# ESC.net
KiCad netlist of a schematic drawn in Altium Designer
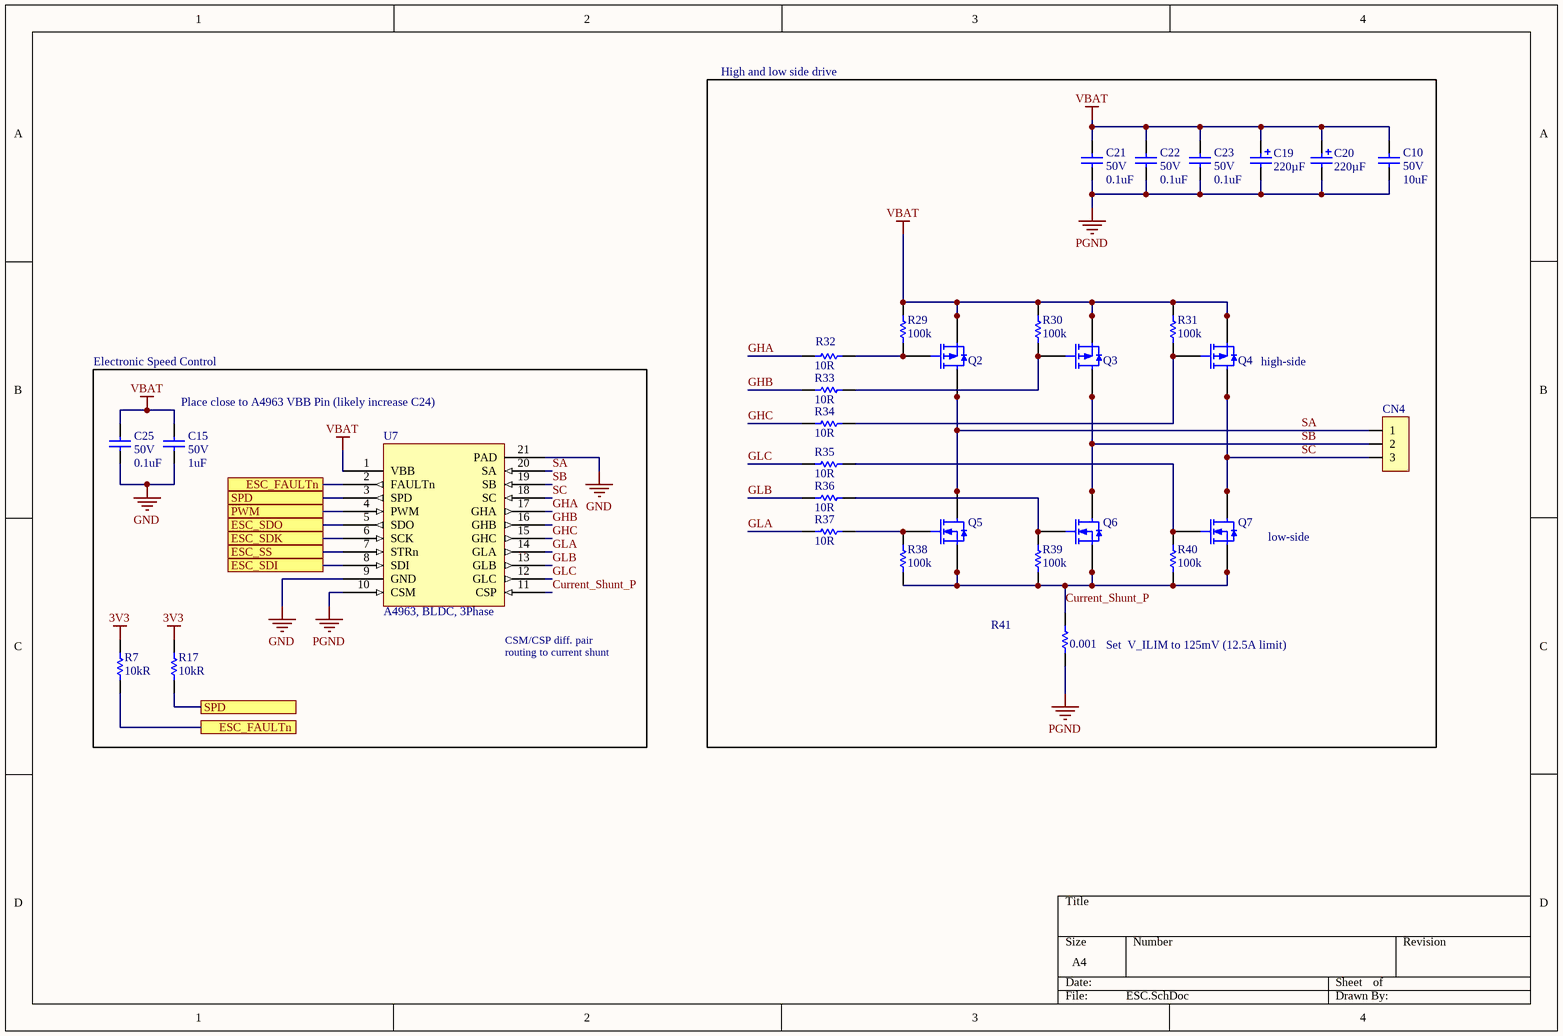
[diagram p0: ESC.SchDoc]

(export (version "E")
  (design (tool "Eeschema 10.0.6"))
  (components
    (comp (ref "C10")
      (value "CL31B106KBHNNNE")
      (footprint "CAPC3216X180X50ML20T30")
      (description "Cap Ceramic 10uF 50V X7R 10% Pad SMD 1206 125°C T/R")
      (fields
        (field (name "VOLTAGE RATING (DC)") "50V")
        (field (name "CAPACITANCE") "10uF")
        (field (name "TOLERANCE") "10%")
      )
      (libsource (lib "AUVIC") (part "CAP-NP-2"))
    )
    (comp (ref "C15")
      (value "CL21B105KBFNNNG")
      (footprint "0803 CAP")
      (description "SAMSUNG ELECTRO-MECHANICS - CL21B105KBFNNNG - MLCC CAPACITORS")
      (fields
        (field (name "CAPACITANCE") "1uF")
        (field (name "TOLERANCE") "10%")
        (field (name "VOLTAGE") "50V")
      )
      (libsource (lib "") (part "Symbol_3"))
    )
    (comp (ref "C19")
      (value "220µF")
      (footprint "Radial_CAN_8.3mm_10.5mm")
      (description "Capacitor, Polarized, Aluminum, 50V")
      (fields
        (field (name "Comment") "220uF, 50V, 20%, Alum, Polarized, SMD")
        (field (name "PUBLISHER") "AUVic")
        (field (name "CREATED BY") "Ashwin Sira")
      )
      (libsource (lib "AUVIC") (part "Symbol"))
    )
    (comp (ref "C20")
      (value "220µF")
      (footprint "Radial_CAN_8.3mm_10.5mm")
      (description "Capacitor, Polarized, Aluminum, 50V")
      (fields
        (field (name "Comment") "220uF, 50V, 20%, Alum, Polarized, SMD")
        (field (name "PUBLISHER") "AUVic")
        (field (name "CREATED BY") "Ashwin Sira")
      )
      (libsource (lib "AUVIC") (part "Symbol"))
    )
    (comp (ref "C21")
      (value "CL10B104JB8NNNC")
      (footprint "FP-CL10-0_1-MFG")
      (description "CAP CER 0.1UF 50V X7R 0603")
      (fields
        (field (name "TOLERANCE") "5%")
        (field (name "VOLTAGE") "50V")
        (field (name "CAPACITANCE") "0.1uF")
      )
      (libsource (lib "AUVIC") (part "CAP-NP-2"))
    )
    (comp (ref "C22")
      (value "CL10B104JB8NNNC")
      (footprint "FP-CL10-0_1-MFG")
      (description "CAP CER 0.1UF 50V X7R 0603")
      (fields
        (field (name "TOLERANCE") "5%")
        (field (name "VOLTAGE") "50V")
        (field (name "CAPACITANCE") "0.1uF")
      )
      (libsource (lib "AUVIC") (part "CAP-NP-2"))
    )
    (comp (ref "C23")
      (value "CL10B104JB8NNNC")
      (footprint "FP-CL10-0_1-MFG")
      (description "CAP CER 0.1UF 50V X7R 0603")
      (fields
        (field (name "TOLERANCE") "5%")
        (field (name "VOLTAGE") "50V")
        (field (name "CAPACITANCE") "0.1uF")
      )
      (libsource (lib "AUVIC") (part "CAP-NP-2"))
    )
    (comp (ref "C25")
      (value "CL10B104JB8NNNC")
      (footprint "FP-CL10-0_1-MFG")
      (description "CAP CER 0.1UF 50V X7R 0603")
      (fields
        (field (name "TOLERANCE") "5%")
        (field (name "VOLTAGE") "50V")
        (field (name "CAPACITANCE") "0.1uF")
      )
      (libsource (lib "AUVIC") (part "CAP-NP-2"))
    )
    (comp (ref "CN4")
      (value "3x1, Terminal Block, Pitch: 5mm, Screw, THT")
      (footprint "3x1, Terminal Block, Pitch: 5mm, Screw, THT")
      (fields (field (name "PUBLISHER") "AUVic, Ashwin Sira") (field (name "REVIEWED BY") "*"))
      (libsource (lib "") (part "Symbol_4"))
    )
    (comp (ref "Q2")
      (value "SI7625DN-T1-GE3")
      (footprint "PowerPAK 1212-8")
      (description "P-Channel 30V 35A (Tc) 3.7W (Ta), 52W (Tc) Surface Mount PowerPAK® 1212-8")
      (fields (field (name "CREATED BY") "Poorna Chander Kalidas"))
      (libsource (lib "") (part "Symbol_1"))
    )
    (comp (ref "Q3")
      (value "SI7625DN-T1-GE3")
      (footprint "PowerPAK 1212-8")
      (description "P-Channel 30V 35A (Tc) 3.7W (Ta), 52W (Tc) Surface Mount PowerPAK® 1212-8")
      (fields (field (name "CREATED BY") "Poorna Chander Kalidas"))
      (libsource (lib "") (part "Symbol_1"))
    )
    (comp (ref "Q4")
      (value "SI7625DN-T1-GE3")
      (footprint "PowerPAK 1212-8")
      (description "P-Channel 30V 35A (Tc) 3.7W (Ta), 52W (Tc) Surface Mount PowerPAK® 1212-8")
      (fields (field (name "CREATED BY") "Poorna Chander Kalidas"))
      (libsource (lib "") (part "Symbol_1"))
    )
    (comp (ref "Q5")
      (value "SIS476DN-T1-GE3")
      (footprint "PowerPAK 1212-8")
      (description "N-Channel 30V 40A (Tc) 3.7W (Ta), 52W (Tc) Surface Mount PowerPAK® 1212-8")
      (fields (field (name "CREATED BY") "Poorna Chander Kalidas"))
      (libsource (lib "AUVIC") (part "SIS476DN-T1-GE3"))
    )
    (comp (ref "Q6")
      (value "SIS476DN-T1-GE3")
      (footprint "PowerPAK 1212-8")
      (description "N-Channel 30V 40A (Tc) 3.7W (Ta), 52W (Tc) Surface Mount PowerPAK® 1212-8")
      (fields (field (name "CREATED BY") "Poorna Chander Kalidas"))
      (libsource (lib "AUVIC") (part "SIS476DN-T1-GE3"))
    )
    (comp (ref "Q7")
      (value "SIS476DN-T1-GE3")
      (footprint "PowerPAK 1212-8")
      (description "N-Channel 30V 40A (Tc) 3.7W (Ta), 52W (Tc) Surface Mount PowerPAK® 1212-8")
      (fields (field (name "CREATED BY") "Poorna Chander Kalidas"))
      (libsource (lib "AUVIC") (part "SIS476DN-T1-GE3"))
    )
    (comp (ref "R7")
      (value "RC0603FR-0710KL")
      (footprint "RESC1608X55X25ML10T15")
      (description "Res General Purpose Thick Film 0603 10K Ohm 1% 1/10W ±100ppm/°C Molded SMD Paper T/R")
      (fields (field (name "RESISTANCE") "10kR") (field (name "TOLERANCE") "1%"))
      (libsource (lib "AUVIC") (part "RES-2"))
    )
    (comp (ref "R17")
      (value "RC0603FR-0710KL")
      (footprint "RESC1608X55X25ML10T15")
      (description "Res General Purpose Thick Film 0603 10K Ohm 1% 1/10W ±100ppm/°C Molded SMD Paper T/R")
      (fields (field (name "RESISTANCE") "10kR") (field (name "TOLERANCE") "1%"))
      (libsource (lib "AUVIC") (part "RES-2"))
    )
    (comp (ref "R29")
      (value "100k")
      (footprint "RESC1608N(0603\")")
      (description "100kR, 1%, 1/10W, 0603 SMD")
      (fields (field (name "MADE BY") "Andy Bates"))
      (libsource (lib "") (part "Symbol_2"))
    )
    (comp (ref "R30")
      (value "100k")
      (footprint "RESC1608N(0603\")")
      (description "100kR, 1%, 1/10W, 0603 SMD")
      (fields (field (name "MADE BY") "Andy Bates"))
      (libsource (lib "") (part "Symbol_2"))
    )
    (comp (ref "R31")
      (value "100k")
      (footprint "RESC1608N(0603\")")
      (description "100kR, 1%, 1/10W, 0603 SMD")
      (fields (field (name "MADE BY") "Andy Bates"))
      (libsource (lib "") (part "Symbol_2"))
    )
    (comp (ref "R32")
      (value "ERJ3EKF10R0V")
      (footprint "FP-ERJ3EK-IPC_A")
      (fields (field (name "RESISTANCE") "10R") (field (name "TOLERANCE") "1%"))
      (libsource (lib "AUVIC") (part "RES"))
    )
    (comp (ref "R33")
      (value "ERJ3EKF10R0V")
      (footprint "FP-ERJ3EK-IPC_A")
      (fields (field (name "RESISTANCE") "10R") (field (name "TOLERANCE") "1%"))
      (libsource (lib "AUVIC") (part "RES"))
    )
    (comp (ref "R34")
      (value "ERJ3EKF10R0V")
      (footprint "FP-ERJ3EK-IPC_A")
      (fields (field (name "RESISTANCE") "10R") (field (name "TOLERANCE") "1%"))
      (libsource (lib "AUVIC") (part "RES"))
    )
    (comp (ref "R35")
      (value "ERJ3EKF10R0V")
      (footprint "FP-ERJ3EK-IPC_A")
      (fields (field (name "RESISTANCE") "10R") (field (name "TOLERANCE") "1%"))
      (libsource (lib "AUVIC") (part "RES"))
    )
    (comp (ref "R36")
      (value "ERJ3EKF10R0V")
      (footprint "FP-ERJ3EK-IPC_A")
      (fields (field (name "RESISTANCE") "10R") (field (name "TOLERANCE") "1%"))
      (libsource (lib "AUVIC") (part "RES"))
    )
    (comp (ref "R37")
      (value "ERJ3EKF10R0V")
      (footprint "FP-ERJ3EK-IPC_A")
      (fields (field (name "RESISTANCE") "10R") (field (name "TOLERANCE") "1%"))
      (libsource (lib "AUVIC") (part "RES"))
    )
    (comp (ref "R38")
      (value "100k")
      (footprint "RESC1608N(0603\")")
      (description "100kR, 1%, 1/10W, 0603 SMD")
      (fields (field (name "MADE BY") "Andy Bates"))
      (libsource (lib "") (part "Symbol_2"))
    )
    (comp (ref "R39")
      (value "100k")
      (footprint "RESC1608N(0603\")")
      (description "100kR, 1%, 1/10W, 0603 SMD")
      (fields (field (name "MADE BY") "Andy Bates"))
      (libsource (lib "") (part "Symbol_2"))
    )
    (comp (ref "R40")
      (value "100k")
      (footprint "RESC1608N(0603\")")
      (description "100kR, 1%, 1/10W, 0603 SMD")
      (fields (field (name "MADE BY") "Andy Bates"))
      (libsource (lib "") (part "Symbol_2"))
    )
    (comp (ref "R41")
      (value "0.001")
      (footprint "RESC6332N(2512\")")
      (description "Res 0.001 Ohm 1% 3W 2512")
      (fields (field (name "Comment") "CSRL3-0R001F8"))
      (libsource (lib "") (part "Symbol_2"))
    )
    (comp (ref "U7")
      (value "A4963, BLDC, 3Phase")
      (footprint "TSOP65P640X120_HS-21M")
      (description "A4963, BLDC, 3 Phase, Sensorless")
      (fields (field (name "CREATED BY") "Poorna Chander Kalidas"))
      (libsource (lib "AUVIC") (part "A4963, BLDC, 3Phase"))
    )
  )
  (nets
    (net (code "1") (name "/Current_Shunt_P") (class "Default")
      (node (ref "Q5") (pin "1") (pinfunction "Source_1") (pintype "passive"))
      (node (ref "Q5") (pin "2") (pinfunction "Source_2") (pintype "passive"))
      (node (ref "Q5") (pin "3") (pinfunction "Source_3") (pintype "passive"))
      (node (ref "Q6") (pin "1") (pinfunction "Source_1") (pintype "passive"))
      (node (ref "Q6") (pin "2") (pinfunction "Source_2") (pintype "passive"))
      (node (ref "Q6") (pin "3") (pinfunction "Source_3") (pintype "passive"))
      (node (ref "Q7") (pin "1") (pinfunction "Source_1") (pintype "passive"))
      (node (ref "Q7") (pin "2") (pinfunction "Source_2") (pintype "passive"))
      (node (ref "Q7") (pin "3") (pinfunction "Source_3") (pintype "passive"))
      (node (ref "R38") (pin "1") (pinfunction "1_1") (pintype "passive"))
      (node (ref "R39") (pin "1") (pinfunction "1_1") (pintype "passive"))
      (node (ref "R40") (pin "1") (pinfunction "1_1") (pintype "passive"))
      (node (ref "R41") (pin "2") (pinfunction "2_2") (pintype "passive"))
      (node (ref "U7") (pin "11") (pinfunction "CSP_11") (pintype "input"))
    )
    (net (code "2") (name "/ESC_FAULTn") (class "Default")
      (node (ref "R7") (pin "2") (pinfunction "2_2") (pintype "passive"))
      (node (ref "U7") (pin "2") (pinfunction "FAULTn_2") (pintype "output"))
    )
    (net (code "3") (name "/ESC_SDI") (class "Default")
      (node (ref "U7") (pin "8") (pinfunction "SDI_8") (pintype "input"))
    )
    (net (code "4") (name "/ESC_SDK") (class "Default")
      (node (ref "U7") (pin "6") (pinfunction "SCK_6") (pintype "input"))
    )
    (net (code "5") (name "/ESC_SDO") (class "Default")
      (node (ref "U7") (pin "5") (pinfunction "SDO_5") (pintype "output"))
    )
    (net (code "6") (name "/ESC_SS") (class "Default")
      (node (ref "U7") (pin "7") (pinfunction "STRn_7") (pintype "input"))
    )
    (net (code "7") (name "/GHA") (class "Default")
      (node (ref "R32") (pin "1") (pinfunction "1_1") (pintype "passive"))
      (node (ref "U7") (pin "17") (pinfunction "GHA_17") (pintype "output"))
    )
    (net (code "8") (name "/GHB") (class "Default")
      (node (ref "R33") (pin "1") (pinfunction "1_1") (pintype "passive"))
      (node (ref "U7") (pin "16") (pinfunction "GHB_16") (pintype "output"))
    )
    (net (code "9") (name "/GHC") (class "Default")
      (node (ref "R34") (pin "1") (pinfunction "1_1") (pintype "passive"))
      (node (ref "U7") (pin "15") (pinfunction "GHC_15") (pintype "output"))
    )
    (net (code "10") (name "/GLA") (class "Default")
      (node (ref "R37") (pin "1") (pinfunction "1_1") (pintype "passive"))
      (node (ref "U7") (pin "14") (pinfunction "GLA_14") (pintype "output"))
    )
    (net (code "11") (name "/GLB") (class "Default")
      (node (ref "R36") (pin "1") (pinfunction "1_1") (pintype "passive"))
      (node (ref "U7") (pin "13") (pinfunction "GLB_13") (pintype "output"))
    )
    (net (code "12") (name "/GLC") (class "Default")
      (node (ref "R35") (pin "1") (pinfunction "1_1") (pintype "passive"))
      (node (ref "U7") (pin "12") (pinfunction "GLC_12") (pintype "output"))
    )
    (net (code "13") (name "/PWM") (class "Default")
      (node (ref "U7") (pin "4") (pinfunction "PWM_4") (pintype "input"))
    )
    (net (code "14") (name "/SA") (class "Default")
      (node (ref "CN4") (pin "1") (pinfunction "1_1") (pintype "passive"))
      (node (ref "Q2") (pin "5") (pinfunction "Drain_5") (pintype "passive"))
      (node (ref "Q2") (pin "6") (pinfunction "Drain_6") (pintype "passive"))
      (node (ref "Q2") (pin "7") (pinfunction "Drain_7") (pintype "passive"))
      (node (ref "Q2") (pin "8") (pinfunction "Drain_8") (pintype "passive"))
      (node (ref "Q2") (pin "9") (pinfunction "Drain_9") (pintype "passive"))
      (node (ref "Q5") (pin "5") (pinfunction "Drain_5") (pintype "passive"))
      (node (ref "Q5") (pin "6") (pinfunction "Drain_6") (pintype "passive"))
      (node (ref "Q5") (pin "7") (pinfunction "Drain_7") (pintype "passive"))
      (node (ref "Q5") (pin "8") (pinfunction "Drain_8") (pintype "passive"))
      (node (ref "Q5") (pin "9") (pinfunction "Drain_9") (pintype "passive"))
      (node (ref "U7") (pin "20") (pinfunction "SA_20") (pintype "input"))
    )
    (net (code "15") (name "/SB") (class "Default")
      (node (ref "CN4") (pin "2") (pinfunction "2_2") (pintype "passive"))
      (node (ref "Q3") (pin "5") (pinfunction "Drain_5") (pintype "passive"))
      (node (ref "Q3") (pin "6") (pinfunction "Drain_6") (pintype "passive"))
      (node (ref "Q3") (pin "7") (pinfunction "Drain_7") (pintype "passive"))
      (node (ref "Q3") (pin "8") (pinfunction "Drain_8") (pintype "passive"))
      (node (ref "Q3") (pin "9") (pinfunction "Drain_9") (pintype "passive"))
      (node (ref "Q6") (pin "5") (pinfunction "Drain_5") (pintype "passive"))
      (node (ref "Q6") (pin "6") (pinfunction "Drain_6") (pintype "passive"))
      (node (ref "Q6") (pin "7") (pinfunction "Drain_7") (pintype "passive"))
      (node (ref "Q6") (pin "8") (pinfunction "Drain_8") (pintype "passive"))
      (node (ref "Q6") (pin "9") (pinfunction "Drain_9") (pintype "passive"))
      (node (ref "U7") (pin "19") (pinfunction "SB_19") (pintype "input"))
    )
    (net (code "16") (name "/SC") (class "Default")
      (node (ref "CN4") (pin "3") (pinfunction "3_3") (pintype "passive"))
      (node (ref "Q4") (pin "5") (pinfunction "Drain_5") (pintype "passive"))
      (node (ref "Q4") (pin "6") (pinfunction "Drain_6") (pintype "passive"))
      (node (ref "Q4") (pin "7") (pinfunction "Drain_7") (pintype "passive"))
      (node (ref "Q4") (pin "8") (pinfunction "Drain_8") (pintype "passive"))
      (node (ref "Q4") (pin "9") (pinfunction "Drain_9") (pintype "passive"))
      (node (ref "Q7") (pin "5") (pinfunction "Drain_5") (pintype "passive"))
      (node (ref "Q7") (pin "6") (pinfunction "Drain_6") (pintype "passive"))
      (node (ref "Q7") (pin "7") (pinfunction "Drain_7") (pintype "passive"))
      (node (ref "Q7") (pin "8") (pinfunction "Drain_8") (pintype "passive"))
      (node (ref "Q7") (pin "9") (pinfunction "Drain_9") (pintype "passive"))
      (node (ref "U7") (pin "18") (pinfunction "SC_18") (pintype "input"))
    )
    (net (code "17") (name "/SPD") (class "Default")
      (node (ref "R17") (pin "2") (pinfunction "2_2") (pintype "passive"))
      (node (ref "U7") (pin "3") (pinfunction "SPD_3") (pintype "output"))
    )
    (net (code "18") (name "3V3") (class "Default")
      (node (ref "R17") (pin "1") (pinfunction "1_1") (pintype "passive"))
      (node (ref "R7") (pin "1") (pinfunction "1_1") (pintype "passive"))
    )
    (net (code "19") (name "GND") (class "Default")
      (node (ref "C15") (pin "1") (pinfunction "1_1") (pintype "passive"))
      (node (ref "C25") (pin "1") (pinfunction "1_1") (pintype "passive"))
      (node (ref "U7") (pin "21") (pinfunction "PAD_21") (pintype "power_in"))
      (node (ref "U7") (pin "9") (pinfunction "GND_9") (pintype "power_in"))
    )
    (net (code "20") (name "Net-(Q2-Gate)") (class "Default")
      (node (ref "Q2") (pin "4") (pinfunction "Gate_4") (pintype "passive"))
      (node (ref "R29") (pin "1") (pinfunction "1_1") (pintype "passive"))
      (node (ref "R32") (pin "2") (pinfunction "2_2") (pintype "passive"))
    )
    (net (code "21") (name "Net-(Q3-Gate)") (class "Default")
      (node (ref "Q3") (pin "4") (pinfunction "Gate_4") (pintype "passive"))
      (node (ref "R30") (pin "1") (pinfunction "1_1") (pintype "passive"))
      (node (ref "R33") (pin "2") (pinfunction "2_2") (pintype "passive"))
    )
    (net (code "22") (name "Net-(Q4-Gate)") (class "Default")
      (node (ref "Q4") (pin "4") (pinfunction "Gate_4") (pintype "passive"))
      (node (ref "R31") (pin "1") (pinfunction "1_1") (pintype "passive"))
      (node (ref "R34") (pin "2") (pinfunction "2_2") (pintype "passive"))
    )
    (net (code "23") (name "Net-(Q5-Gate)") (class "Default")
      (node (ref "Q5") (pin "4") (pinfunction "Gate_4") (pintype "passive"))
      (node (ref "R37") (pin "2") (pinfunction "2_2") (pintype "passive"))
      (node (ref "R38") (pin "2") (pinfunction "2_2") (pintype "passive"))
    )
    (net (code "24") (name "Net-(Q6-Gate)") (class "Default")
      (node (ref "Q6") (pin "4") (pinfunction "Gate_4") (pintype "passive"))
      (node (ref "R36") (pin "2") (pinfunction "2_2") (pintype "passive"))
      (node (ref "R39") (pin "2") (pinfunction "2_2") (pintype "passive"))
    )
    (net (code "25") (name "Net-(Q7-Gate)") (class "Default")
      (node (ref "Q7") (pin "4") (pinfunction "Gate_4") (pintype "passive"))
      (node (ref "R35") (pin "2") (pinfunction "2_2") (pintype "passive"))
      (node (ref "R40") (pin "2") (pinfunction "2_2") (pintype "passive"))
    )
    (net (code "26") (name "PGND") (class "Default")
      (node (ref "C10") (pin "1") (pinfunction "1_1") (pintype "passive"))
      (node (ref "C19") (pin "2") (pinfunction "Cathode_2") (pintype "passive"))
      (node (ref "C20") (pin "2") (pinfunction "Cathode_2") (pintype "passive"))
      (node (ref "C21") (pin "1") (pinfunction "1_1") (pintype "passive"))
      (node (ref "C22") (pin "1") (pinfunction "1_1") (pintype "passive"))
      (node (ref "C23") (pin "1") (pinfunction "1_1") (pintype "passive"))
      (node (ref "R41") (pin "1") (pinfunction "1_1") (pintype "passive"))
      (node (ref "U7") (pin "10") (pinfunction "CSM_10") (pintype "input"))
    )
    (net (code "27") (name "VBAT") (class "Default")
      (node (ref "C10") (pin "2") (pinfunction "2_2") (pintype "passive"))
      (node (ref "C15") (pin "2") (pinfunction "2_2") (pintype "passive"))
      (node (ref "C19") (pin "1") (pinfunction "Anode_1") (pintype "passive"))
      (node (ref "C20") (pin "1") (pinfunction "Anode_1") (pintype "passive"))
      (node (ref "C21") (pin "2") (pinfunction "2_2") (pintype "passive"))
      (node (ref "C22") (pin "2") (pinfunction "2_2") (pintype "passive"))
      (node (ref "C23") (pin "2") (pinfunction "2_2") (pintype "passive"))
      (node (ref "C25") (pin "2") (pinfunction "2_2") (pintype "passive"))
      (node (ref "Q2") (pin "1") (pinfunction "Source_1") (pintype "passive"))
      (node (ref "Q2") (pin "2") (pinfunction "Source_2") (pintype "passive"))
      (node (ref "Q2") (pin "3") (pinfunction "Source_3") (pintype "passive"))
      (node (ref "Q3") (pin "1") (pinfunction "Source_1") (pintype "passive"))
      (node (ref "Q3") (pin "2") (pinfunction "Source_2") (pintype "passive"))
      (node (ref "Q3") (pin "3") (pinfunction "Source_3") (pintype "passive"))
      (node (ref "Q4") (pin "1") (pinfunction "Source_1") (pintype "passive"))
      (node (ref "Q4") (pin "2") (pinfunction "Source_2") (pintype "passive"))
      (node (ref "Q4") (pin "3") (pinfunction "Source_3") (pintype "passive"))
      (node (ref "R29") (pin "2") (pinfunction "2_2") (pintype "passive"))
      (node (ref "R30") (pin "2") (pinfunction "2_2") (pintype "passive"))
      (node (ref "R31") (pin "2") (pinfunction "2_2") (pintype "passive"))
      (node (ref "U7") (pin "1") (pinfunction "VBB_1") (pintype "power_in"))
    )
  )
)
